# Licznik_Geigera.net
KiCad netlist of a schematic drawn in EAGLE
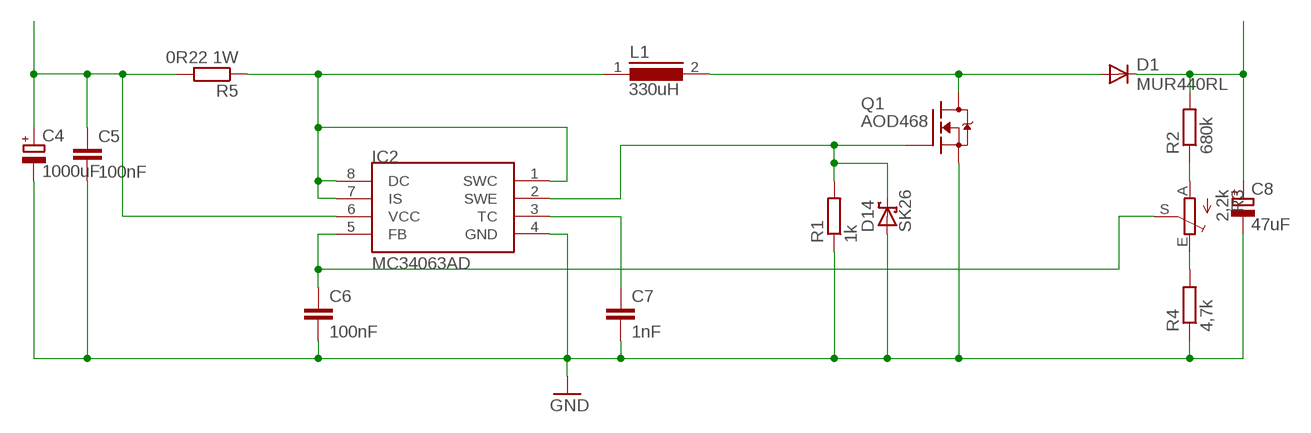
[diagram p0: schematic, sheet 1]

(export (version "E")
  (design (tool "Eeschema 10.0.6"))
  (components
    (comp (ref "C4")
      (value "1000uF")
      (footprint "eagle-import:E5-10,5")
      (libsource (lib "eagle-import") (part "CPOL-EUE5-10.5"))
    )
    (comp (ref "C5")
      (value "100nF")
      (footprint "eagle-import:C1206")
      (libsource (lib "eagle-import") (part "C-EUC1206"))
    )
    (comp (ref "C6")
      (value "100nF")
      (footprint "eagle-import:C1206")
      (libsource (lib "eagle-import") (part "C-EUC1206"))
    )
    (comp (ref "C7")
      (value "1nF")
      (footprint "eagle-import:C1206")
      (libsource (lib "eagle-import") (part "C-EUC1206"))
    )
    (comp (ref "C8")
      (value "47uF")
      (footprint "eagle-import:E5-13")
      (libsource (lib "eagle-import") (part "CPOL-EUE5-13"))
    )
    (comp (ref "D1")
      (value "MUR440RL")
      (footprint "eagle-import:C2673")
      (libsource (lib "eagle-import") (part "MUR440RL"))
    )
    (comp (ref "D14")
      (value "SK26")
      (footprint "eagle-import:SMB")
      (libsource (lib "eagle-import") (part "SCHOTTKY-DIODESMD"))
    )
    (comp (ref "IC2")
      (value "MC34063AD")
      (footprint "eagle-import:SOIC8")
      (libsource (lib "eagle-import") (part "MC34063AD"))
    )
    (comp (ref "L1")
      (value "330uH")
      (footprint "eagle-import:SFT830D")
      (libsource (lib "eagle-import") (part "SFT830D"))
    )
    (comp (ref "Q1")
      (value "AOD468")
      (footprint "eagle-import:DPAK-TO252")
      (libsource (lib "eagle-import") (part "AOD468"))
    )
    (comp (ref "R1")
      (value "1k")
      (footprint "eagle-import:R0805")
      (libsource (lib "eagle-import") (part "R-EU_R0805"))
    )
    (comp (ref "R2")
      (value "680k")
      (footprint "eagle-import:R0805")
      (libsource (lib "eagle-import") (part "R-EU_R0805"))
    )
    (comp (ref "R3")
      (value "2,2k")
      (footprint "eagle-import:CA6V")
      (libsource (lib "eagle-import") (part "TRIM_EU-CA6V"))
    )
    (comp (ref "R4")
      (value "4,7k")
      (footprint "eagle-import:R0805")
      (libsource (lib "eagle-import") (part "R-EU_R0805"))
    )
    (comp (ref "R5")
      (value "0R22 1W")
      (footprint "eagle-import:0411_15")
      (libsource (lib "eagle-import") (part "R-EU_0411/15"))
    )
  )
  (nets
    (net (code "1") (name "GND") (class "Default")
      (node (ref "C4") (pin "-") (pinfunction "-_-") (pintype "passive"))
      (node (ref "C5") (pin "2") (pinfunction "2_2") (pintype "passive"))
      (node (ref "C6") (pin "2") (pinfunction "2_2") (pintype "passive"))
      (node (ref "C7") (pin "2") (pinfunction "2_2") (pintype "passive"))
      (node (ref "C8") (pin "-") (pinfunction "-_-") (pintype "passive"))
      (node (ref "D14") (pin "A") (pinfunction "A_A") (pintype "passive"))
      (node (ref "IC2") (pin "4") (pinfunction "GND_4") (pintype "passive"))
      (node (ref "Q1") (pin "3") (pinfunction "S_3") (pintype "passive"))
      (node (ref "R1") (pin "1") (pinfunction "1_1") (pintype "passive"))
      (node (ref "R4") (pin "1") (pinfunction "1_1") (pintype "passive"))
    )
    (net (code "2") (name "Net-(C8-Pad+)") (class "Default")
      (node (ref "C8") (pin "+") (pinfunction "+_+") (pintype "passive"))
      (node (ref "D1") (pin "C") (pinfunction "C_C") (pintype "passive"))
      (node (ref "R2") (pin "2") (pinfunction "2_2") (pintype "passive"))
    )
    (net (code "3") (name "Net-(IC2-DC)") (class "Default")
      (node (ref "IC2") (pin "1") (pinfunction "SWC_1") (pintype "passive"))
      (node (ref "IC2") (pin "7") (pinfunction "IS_7") (pintype "passive"))
      (node (ref "IC2") (pin "8") (pinfunction "DC_8") (pintype "passive"))
      (node (ref "L1") (pin "1") (pinfunction "1_1") (pintype "passive"))
      (node (ref "R5") (pin "1") (pinfunction "1_1") (pintype "passive"))
    )
    (net (code "4") (name "Net-(IC2-FB)") (class "Default")
      (node (ref "C6") (pin "1") (pinfunction "1_1") (pintype "passive"))
      (node (ref "IC2") (pin "5") (pinfunction "FB_5") (pintype "passive"))
      (node (ref "R3") (pin "S") (pinfunction "S_S") (pintype "passive"))
    )
    (net (code "5") (name "Net-(IC2-SWE)") (class "Default")
      (node (ref "D14") (pin "C") (pinfunction "C_C") (pintype "passive"))
      (node (ref "IC2") (pin "2") (pinfunction "SWE_2") (pintype "passive"))
      (node (ref "Q1") (pin "1") (pinfunction "G_1") (pintype "passive"))
      (node (ref "R1") (pin "2") (pinfunction "2_2") (pintype "passive"))
    )
    (net (code "6") (name "Net-(IC2-TC)") (class "Default")
      (node (ref "C7") (pin "1") (pinfunction "1_1") (pintype "passive"))
      (node (ref "IC2") (pin "3") (pinfunction "TC_3") (pintype "passive"))
    )
    (net (code "7") (name "Net-(IC2-VCC)") (class "Default")
      (node (ref "C4") (pin "+") (pinfunction "+_+") (pintype "passive"))
      (node (ref "C5") (pin "1") (pinfunction "1_1") (pintype "passive"))
      (node (ref "IC2") (pin "6") (pinfunction "VCC_6") (pintype "passive"))
      (node (ref "R5") (pin "2") (pinfunction "2_2") (pintype "passive"))
    )
    (net (code "8") (name "Net-(Q1-D)") (class "Default")
      (node (ref "D1") (pin "A") (pinfunction "A_A") (pintype "passive"))
      (node (ref "L1") (pin "2") (pinfunction "2_2") (pintype "passive"))
      (node (ref "Q1") (pin "2") (pinfunction "D_2") (pintype "passive"))
    )
    (net (code "9") (name "Net-(R2-Pad1)") (class "Default")
      (node (ref "R2") (pin "1") (pinfunction "1_1") (pintype "passive"))
      (node (ref "R3") (pin "A") (pinfunction "A_A") (pintype "passive"))
    )
    (net (code "10") (name "Net-(R3-PadE)") (class "Default")
      (node (ref "R3") (pin "E") (pinfunction "E_E") (pintype "passive"))
      (node (ref "R4") (pin "2") (pinfunction "2_2") (pintype "passive"))
    )
  )
)
